# Power.net
KiCad netlist of a schematic drawn in Altium Designer
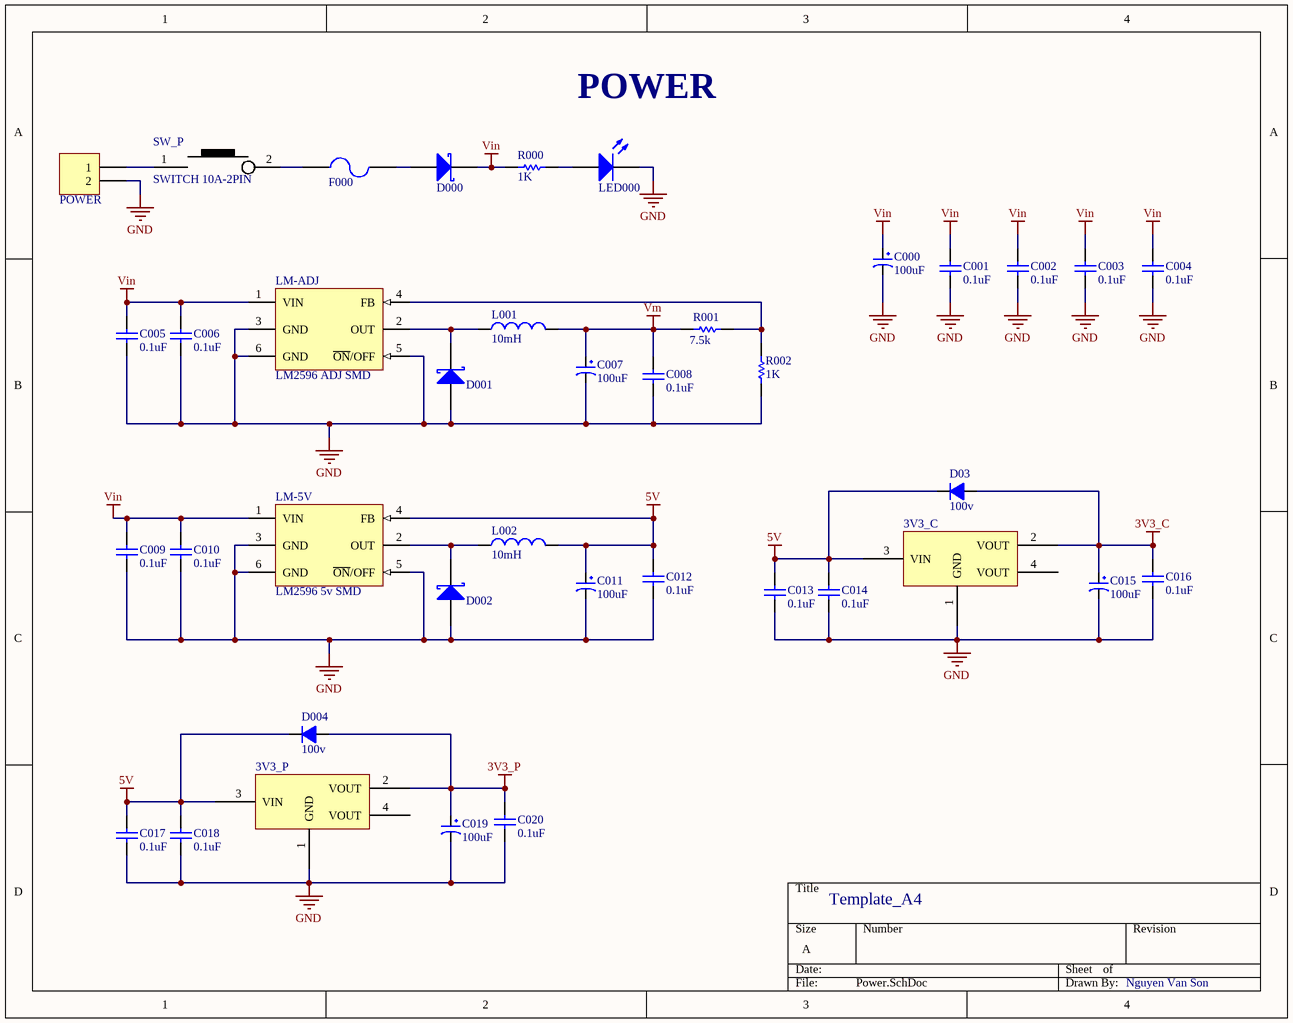
[diagram p0: Power.SchDoc]

(export (version "E")
  (design (tool "Eeschema 10.0.6"))
  (components
    (comp (ref "3V3_C")
      (value "AMS1117-3.3V")
      (footprint "SOT223")
      (description "Dán")
      (libsource (lib "Altium_Lib_by_KhueNguyenCreator") (part "AMS1117 SMD"))
    )
    (comp (ref "3V3_P")
      (value "AMS1117-3.3V")
      (footprint "SOT223")
      (description "Dán")
      (libsource (lib "Altium_Lib_by_KhueNguyenCreator") (part "AMS1117 SMD"))
    )
    (comp (ref "C000")
      (value "100uF")
      (footprint "tu tantalum smd7343")
      (description "Dán")
      (libsource (lib "Altium_Lib_by_KhueNguyenCreator") (part "Tu tantalum 100uF 50V SMD7343"))
    )
    (comp (ref "C001")
      (value "0.1uF")
      (footprint "CAP-SM-0805")
      (description "Capacitor")
      (fields (field (name "Comment") "Cap Non-Pol SMD"))
      (libsource (lib "PIF_Library") (part "Cap Non-Pol SMD"))
    )
    (comp (ref "C002")
      (value "0.1uF")
      (footprint "CAP-SM-0805")
      (description "Capacitor")
      (fields (field (name "Comment") "Cap Non-Pol SMD"))
      (libsource (lib "PIF_Library") (part "Cap Non-Pol SMD"))
    )
    (comp (ref "C003")
      (value "0.1uF")
      (footprint "CAP-SM-0805")
      (description "Capacitor")
      (fields (field (name "Comment") "Cap Non-Pol SMD"))
      (libsource (lib "PIF_Library") (part "Cap Non-Pol SMD"))
    )
    (comp (ref "C004")
      (value "0.1uF")
      (footprint "CAP-SM-0805")
      (description "Capacitor")
      (fields (field (name "Comment") "Cap Non-Pol SMD"))
      (libsource (lib "PIF_Library") (part "Cap Non-Pol SMD"))
    )
    (comp (ref "C005")
      (value "0.1uF")
      (footprint "CAP-SM-0805")
      (description "Capacitor")
      (fields (field (name "Comment") "Cap Non-Pol SMD"))
      (libsource (lib "PIF_Library") (part "Cap Non-Pol SMD"))
    )
    (comp (ref "C006")
      (value "0.1uF")
      (footprint "CAP-SM-0805")
      (description "Capacitor")
      (fields (field (name "Comment") "Cap Non-Pol SMD"))
      (libsource (lib "PIF_Library") (part "Cap Non-Pol SMD"))
    )
    (comp (ref "C007")
      (value "100uF")
      (footprint "tu tantalum smd3528")
      (description "Dán")
      (libsource (lib "Altium_Lib_by_KhueNguyenCreator") (part "Tu tantalum 100uF 50V SMD7343"))
    )
    (comp (ref "C008")
      (value "0.1uF")
      (footprint "CAP-SM-0805")
      (description "Capacitor")
      (fields (field (name "Comment") "Cap Non-Pol SMD"))
      (libsource (lib "PIF_Library") (part "Cap Non-Pol SMD"))
    )
    (comp (ref "C009")
      (value "0.1uF")
      (footprint "CAP-SM-0805")
      (description "Capacitor")
      (fields (field (name "Comment") "Cap Non-Pol SMD"))
      (libsource (lib "PIF_Library") (part "Cap Non-Pol SMD"))
    )
    (comp (ref "C010")
      (value "0.1uF")
      (footprint "CAP-SM-0805")
      (description "Capacitor")
      (fields (field (name "Comment") "Cap Non-Pol SMD"))
      (libsource (lib "PIF_Library") (part "Cap Non-Pol SMD"))
    )
    (comp (ref "C011")
      (value "100uF")
      (footprint "tu tantalum smd3528")
      (description "Dán")
      (libsource (lib "Altium_Lib_by_KhueNguyenCreator") (part "Tu tantalum 100uF 10V SMD6032"))
    )
    (comp (ref "C012")
      (value "0.1uF")
      (footprint "CAP-SM-0805")
      (description "Capacitor")
      (fields (field (name "Comment") "Cap Non-Pol SMD"))
      (libsource (lib "PIF_Library") (part "Cap Non-Pol SMD"))
    )
    (comp (ref "C013")
      (value "0.1uF")
      (footprint "CAP-SM-0805")
      (description "Capacitor")
      (fields (field (name "Comment") "Cap Non-Pol SMD"))
      (libsource (lib "PIF_Library") (part "Cap Non-Pol SMD"))
    )
    (comp (ref "C014")
      (value "0.1uF")
      (footprint "CAP-SM-0805")
      (description "Capacitor")
      (fields (field (name "Comment") "Cap Non-Pol SMD"))
      (libsource (lib "PIF_Library") (part "Cap Non-Pol SMD"))
    )
    (comp (ref "C015")
      (value "100uF")
      (footprint "tu tantalum smd3528")
      (description "Dán")
      (libsource (lib "Altium_Lib_by_KhueNguyenCreator") (part "Tu tantalum 100uF 6.3V SMD3528"))
    )
    (comp (ref "C016")
      (value "0.1uF")
      (footprint "CAP-SM-0805")
      (description "Capacitor")
      (fields (field (name "Comment") "Cap Non-Pol SMD"))
      (libsource (lib "PIF_Library") (part "Cap Non-Pol SMD"))
    )
    (comp (ref "C017")
      (value "0.1uF")
      (footprint "CAP-SM-0805")
      (description "Capacitor")
      (fields (field (name "Comment") "Cap Non-Pol SMD"))
      (libsource (lib "PIF_Library") (part "Cap Non-Pol SMD"))
    )
    (comp (ref "C018")
      (value "0.1uF")
      (footprint "CAP-SM-0805")
      (description "Capacitor")
      (fields (field (name "Comment") "Cap Non-Pol SMD"))
      (libsource (lib "PIF_Library") (part "Cap Non-Pol SMD"))
    )
    (comp (ref "C019")
      (value "100uF")
      (footprint "tu tantalum smd3528")
      (description "Dán")
      (libsource (lib "Altium_Lib_by_KhueNguyenCreator") (part "Tu tantalum 100uF 6.3V SMD3528"))
    )
    (comp (ref "C020")
      (value "0.1uF")
      (footprint "CAP-SM-0805")
      (description "Capacitor")
      (fields (field (name "Comment") "Cap Non-Pol SMD"))
      (libsource (lib "PIF_Library") (part "Cap Non-Pol SMD"))
    )
    (comp (ref "D000")
      (value "D Schottky")
      (footprint "SS34")
      (description "Schottky Diode")
      (fields (field (name "PUBLISHER") "Altium Limited"))
      (libsource (lib "PIF_Library") (part "D Schottky"))
    )
    (comp (ref "D001")
      (value "D Schottky")
      (footprint "SS34")
      (description "Schottky Diode")
      (fields (field (name "PUBLISHER") "Altium Limited"))
      (libsource (lib "PIF_Library") (part "D Schottky"))
    )
    (comp (ref "D002")
      (value "D Schottky")
      (footprint "SS34")
      (description "Schottky Diode")
      (fields (field (name "PUBLISHER") "Altium Limited"))
      (libsource (lib "PIF_Library") (part "D Schottky"))
    )
    (comp (ref "D03")
      (value "100v")
      (footprint "DIODE SMA")
      (description "Cắm")
      (libsource (lib "Altium_Lib_by_KhueNguyenCreator") (part "Diode 1N4007"))
    )
    (comp (ref "D004")
      (value "100v")
      (footprint "DIODE SMA")
      (description "Cắm")
      (libsource (lib "Altium_Lib_by_KhueNguyenCreator") (part "Diode 1N4007"))
    )
    (comp (ref "F000") (value "Fuse") (footprint "FUSE SMD") (libsource (lib "PIF_Library") (part "Fuse")))
    (comp (ref "L001")
      (value "10mH")
      (footprint "INDUCTOR 12.5x12.5")
      (description "Inductor")
      (libsource (lib "PIF_Library") (part "Inductor"))
    )
    (comp (ref "L002")
      (value "10mH")
      (footprint "INDUCTOR 12.5x12.5")
      (description "Inductor")
      (libsource (lib "PIF_Library") (part "Inductor"))
    )
    (comp (ref "LED000")
      (value "LED SMD")
      (footprint "LED-5mm")
      (description "LED")
      (libsource (lib "PIF_Library") (part "LED SMD"))
    )
    (comp (ref "LM-5V")
      (value "LM2596 5v SMD")
      (footprint "TO263-5")
      (description "Dán")
      (libsource (lib "Altium_Lib_by_KhueNguyenCreator") (part "LM2576 3.3V SMD"))
    )
    (comp (ref "LM-ADJ")
      (value "LM2596 ADJ SMD")
      (footprint "TO263-5")
      (description "Dán")
      (libsource (lib "Altium_Lib_by_KhueNguyenCreator") (part "LM2576 3.3V SMD"))
    )
    (comp (ref "POWER")
      (value "Domino 2")
      (footprint "DOMINO SMALL 2")
      (description "Domino, 2-Pin")
      (fields (field (name "PUBLISHER") "Altium Limited"))
      (libsource (lib "PIF_Library") (part "Domino 2"))
    )
    (comp (ref "R000")
      (value "1K")
      (footprint "RES-SM-0805")
      (description "Resistor")
      (fields (field (name "Comment") "RESISTOR SMD"))
      (libsource (lib "PIF_Library") (part "RESISTOR SMD"))
    )
    (comp (ref "R001")
      (value "7.5k")
      (footprint "RES-SM-0805")
      (description "Resistor")
      (fields (field (name "Comment") "RESISTOR SMD"))
      (libsource (lib "PIF_Library") (part "RESISTOR SMD"))
    )
    (comp (ref "R002")
      (value "1K")
      (footprint "RES-SM-0805")
      (description "Resistor")
      (fields (field (name "Comment") "RESISTOR SMD"))
      (libsource (lib "PIF_Library") (part "RESISTOR SMD"))
    )
    (comp (ref "SW_P")
      (value "SWITCH 10A-2PIN")
      (footprint "SW_2ARS_TH")
      (description "Rocker Switch SPST 16A (AC), 10A (DC) 250V Panel Mount, Snap-In")
      (fields
        (field (name "MANUFACTURER") "Würth Elektronik")
        (field (name "MANUFACTURER PART NUMBER") "471005264153")
      )
      (libsource (lib "Altium_Lib_by_KhueNguyenCreator") (part "SW1_RS-471005264153-TH"))
    )
  )
  (nets
    (net (code "1") (name "3V3_C") (class "Default")
      (node (ref "3V3_C") (pin "2") (pinfunction "VOUT_2") (pintype "passive"))
      (node (ref "C015") (pin "1") (pinfunction "1_1") (pintype "passive"))
      (node (ref "C016") (pin "2") (pinfunction "2_2") (pintype "passive"))
      (node (ref "D03") (pin "1") (pinfunction "A_1") (pintype "passive"))
    )
    (net (code "2") (name "3V3_P") (class "Default")
      (node (ref "3V3_P") (pin "2") (pinfunction "VOUT_2") (pintype "passive"))
      (node (ref "C019") (pin "1") (pinfunction "1_1") (pintype "passive"))
      (node (ref "C020") (pin "2") (pinfunction "2_2") (pintype "passive"))
      (node (ref "D004") (pin "1") (pinfunction "A_1") (pintype "passive"))
    )
    (net (code "3") (name "5V") (class "Default")
      (node (ref "3V3_C") (pin "3") (pinfunction "VIN_3") (pintype "passive"))
      (node (ref "3V3_P") (pin "3") (pinfunction "VIN_3") (pintype "passive"))
      (node (ref "C011") (pin "1") (pinfunction "1_1") (pintype "passive"))
      (node (ref "C012") (pin "2") (pinfunction "2_2") (pintype "passive"))
      (node (ref "C013") (pin "2") (pinfunction "2_2") (pintype "passive"))
      (node (ref "C014") (pin "2") (pinfunction "2_2") (pintype "passive"))
      (node (ref "C017") (pin "2") (pinfunction "2_2") (pintype "passive"))
      (node (ref "C018") (pin "2") (pinfunction "2_2") (pintype "passive"))
      (node (ref "D004") (pin "2") (pinfunction "K_2") (pintype "passive"))
      (node (ref "D03") (pin "2") (pinfunction "K_2") (pintype "passive"))
      (node (ref "L002") (pin "2") (pinfunction "2_2") (pintype "passive"))
      (node (ref "LM-5V") (pin "4") (pinfunction "FB_4") (pintype "input"))
    )
    (net (code "4") (name "GND") (class "Default")
      (node (ref "3V3_C") (pin "1") (pinfunction "GND_1") (pintype "passive"))
      (node (ref "3V3_P") (pin "1") (pinfunction "GND_1") (pintype "passive"))
      (node (ref "C000") (pin "2") (pinfunction "2_2") (pintype "passive"))
      (node (ref "C001") (pin "1") (pinfunction "1_1") (pintype "passive"))
      (node (ref "C002") (pin "1") (pinfunction "1_1") (pintype "passive"))
      (node (ref "C003") (pin "1") (pinfunction "1_1") (pintype "passive"))
      (node (ref "C004") (pin "1") (pinfunction "1_1") (pintype "passive"))
      (node (ref "C005") (pin "1") (pinfunction "1_1") (pintype "passive"))
      (node (ref "C006") (pin "1") (pinfunction "1_1") (pintype "passive"))
      (node (ref "C007") (pin "2") (pinfunction "2_2") (pintype "passive"))
      (node (ref "C008") (pin "1") (pinfunction "1_1") (pintype "passive"))
      (node (ref "C009") (pin "1") (pinfunction "1_1") (pintype "passive"))
      (node (ref "C010") (pin "1") (pinfunction "1_1") (pintype "passive"))
      (node (ref "C011") (pin "2") (pinfunction "2_2") (pintype "passive"))
      (node (ref "C012") (pin "1") (pinfunction "1_1") (pintype "passive"))
      (node (ref "C013") (pin "1") (pinfunction "1_1") (pintype "passive"))
      (node (ref "C014") (pin "1") (pinfunction "1_1") (pintype "passive"))
      (node (ref "C015") (pin "2") (pinfunction "2_2") (pintype "passive"))
      (node (ref "C016") (pin "1") (pinfunction "1_1") (pintype "passive"))
      (node (ref "C017") (pin "1") (pinfunction "1_1") (pintype "passive"))
      (node (ref "C018") (pin "1") (pinfunction "1_1") (pintype "passive"))
      (node (ref "C019") (pin "2") (pinfunction "2_2") (pintype "passive"))
      (node (ref "C020") (pin "1") (pinfunction "1_1") (pintype "passive"))
      (node (ref "D001") (pin "1") (pinfunction "A_1") (pintype "passive"))
      (node (ref "D002") (pin "1") (pinfunction "A_1") (pintype "passive"))
      (node (ref "LED000") (pin "2") (pinfunction "K_2") (pintype "passive"))
      (node (ref "LM-5V") (pin "3") (pinfunction "GND_3") (pintype "power_in"))
      (node (ref "LM-5V") (pin "5") (pinfunction "~{ON}/OFF_5") (pintype "input"))
      (node (ref "LM-5V") (pin "6") (pinfunction "GND_6") (pintype "passive"))
      (node (ref "LM-ADJ") (pin "3") (pinfunction "GND_3") (pintype "power_in"))
      (node (ref "LM-ADJ") (pin "5") (pinfunction "~{ON}/OFF_5") (pintype "input"))
      (node (ref "LM-ADJ") (pin "6") (pinfunction "GND_6") (pintype "passive"))
      (node (ref "POWER") (pin "2") (pinfunction "2_2") (pintype "passive"))
      (node (ref "R002") (pin "2") (pinfunction "2_2") (pintype "passive"))
    )
    (net (code "5") (name "Net-(D000-A)") (class "Default")
      (node (ref "D000") (pin "1") (pinfunction "A_1") (pintype "passive"))
      (node (ref "F000") (pin "2") (pinfunction "2_2") (pintype "passive"))
    )
    (net (code "6") (name "Net-(D001-K)") (class "Default")
      (node (ref "D001") (pin "2") (pinfunction "K_2") (pintype "passive"))
      (node (ref "L001") (pin "1") (pinfunction "1_1") (pintype "passive"))
      (node (ref "LM-ADJ") (pin "2") (pinfunction "OUT_2") (pintype "power_in"))
    )
    (net (code "7") (name "Net-(D002-K)") (class "Default")
      (node (ref "D002") (pin "2") (pinfunction "K_2") (pintype "passive"))
      (node (ref "L002") (pin "1") (pinfunction "1_1") (pintype "passive"))
      (node (ref "LM-5V") (pin "2") (pinfunction "OUT_2") (pintype "power_in"))
    )
    (net (code "8") (name "Net-(F000-Pad1)") (class "Default")
      (node (ref "F000") (pin "1") (pinfunction "1_1") (pintype "passive"))
      (node (ref "SW_P") (pin "2") (pinfunction "2_2") (pintype "passive"))
    )
    (net (code "9") (name "Net-(LED000-A)") (class "Default")
      (node (ref "LED000") (pin "1") (pinfunction "A_1") (pintype "passive"))
      (node (ref "R000") (pin "2") (pinfunction "2_2") (pintype "passive"))
    )
    (net (code "10") (name "Net-(LM-ADJ-FB)") (class "Default")
      (node (ref "LM-ADJ") (pin "4") (pinfunction "FB_4") (pintype "input"))
      (node (ref "R001") (pin "1") (pinfunction "1_1") (pintype "passive"))
      (node (ref "R002") (pin "1") (pinfunction "1_1") (pintype "passive"))
    )
    (net (code "11") (name "Net-(POWER-Pad1)") (class "Default")
      (node (ref "POWER") (pin "1") (pinfunction "1_1") (pintype "passive"))
      (node (ref "SW_P") (pin "1") (pinfunction "1_1") (pintype "passive"))
    )
    (net (code "12") (name "Vin") (class "Default")
      (node (ref "C000") (pin "1") (pinfunction "1_1") (pintype "passive"))
      (node (ref "C001") (pin "2") (pinfunction "2_2") (pintype "passive"))
      (node (ref "C002") (pin "2") (pinfunction "2_2") (pintype "passive"))
      (node (ref "C003") (pin "2") (pinfunction "2_2") (pintype "passive"))
      (node (ref "C004") (pin "2") (pinfunction "2_2") (pintype "passive"))
      (node (ref "C005") (pin "2") (pinfunction "2_2") (pintype "passive"))
      (node (ref "C006") (pin "2") (pinfunction "2_2") (pintype "passive"))
      (node (ref "C009") (pin "2") (pinfunction "2_2") (pintype "passive"))
      (node (ref "C010") (pin "2") (pinfunction "2_2") (pintype "passive"))
      (node (ref "D000") (pin "2") (pinfunction "K_2") (pintype "passive"))
      (node (ref "LM-5V") (pin "1") (pinfunction "VIN_1") (pintype "power_in"))
      (node (ref "LM-ADJ") (pin "1") (pinfunction "VIN_1") (pintype "power_in"))
      (node (ref "R000") (pin "1") (pinfunction "1_1") (pintype "passive"))
    )
    (net (code "13") (name "Vm") (class "Default")
      (node (ref "C007") (pin "1") (pinfunction "1_1") (pintype "passive"))
      (node (ref "C008") (pin "2") (pinfunction "2_2") (pintype "passive"))
      (node (ref "L001") (pin "2") (pinfunction "2_2") (pintype "passive"))
      (node (ref "R001") (pin "2") (pinfunction "2_2") (pintype "passive"))
    )
    (net (code "14") (name "unconnected-(3V3_C-VOUT-Pad4)") (class "Default")
      (node (ref "3V3_C") (pin "4") (pinfunction "VOUT_4") (pintype "passive"))
    )
    (net (code "15") (name "unconnected-(3V3_P-VOUT-Pad4)") (class "Default")
      (node (ref "3V3_P") (pin "4") (pinfunction "VOUT_4") (pintype "passive"))
    )
  )
)
